# NBP16_Xilinx_Spartan-II_PQ208_Rev1_01.net
KiCad netlist of a schematic drawn in Altium Designer
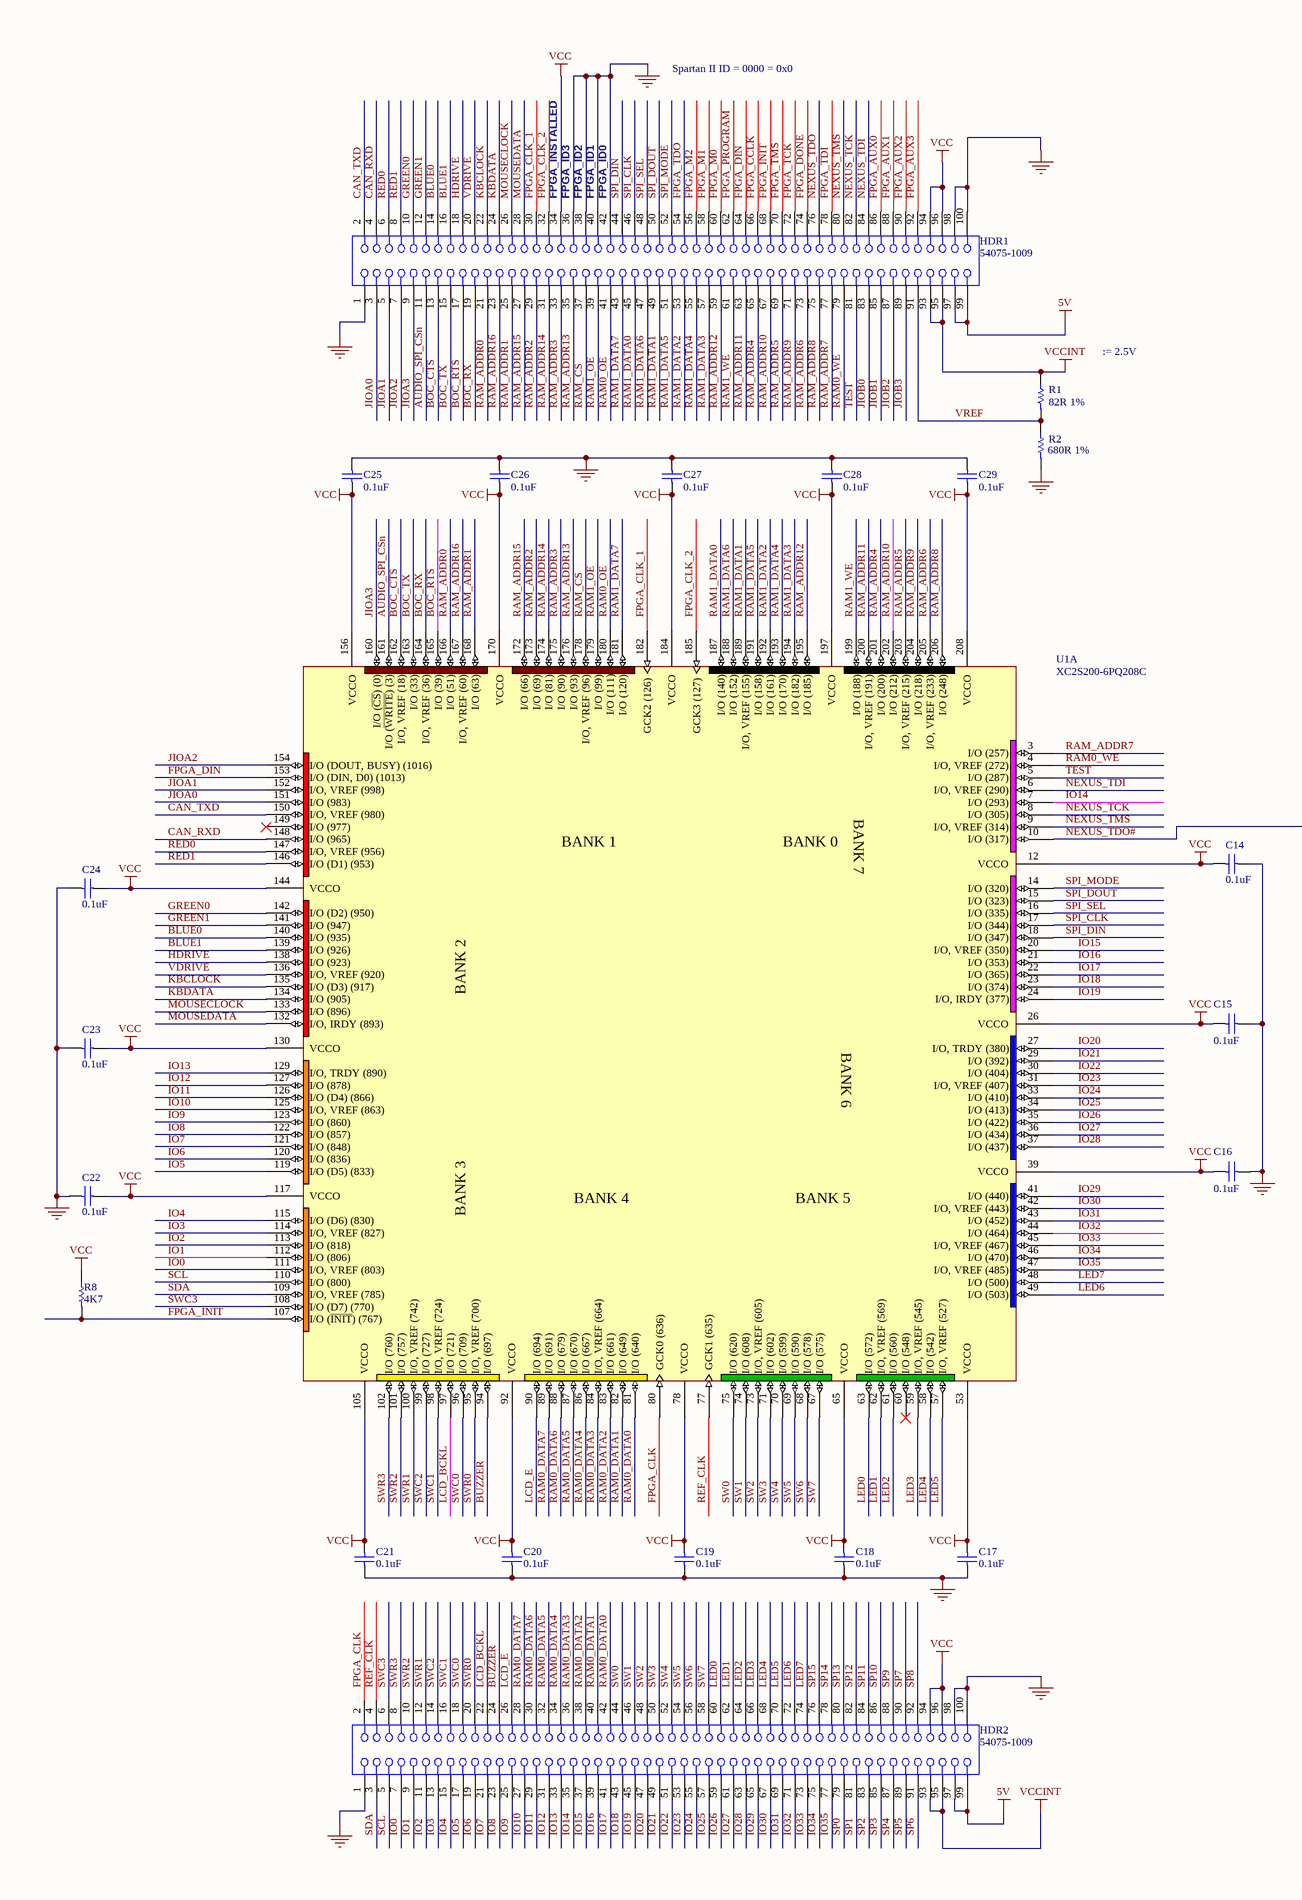
[diagram p0: NBP16 Xilinx Spartan-II PQ208 Rev1.01.SchDoc, left]
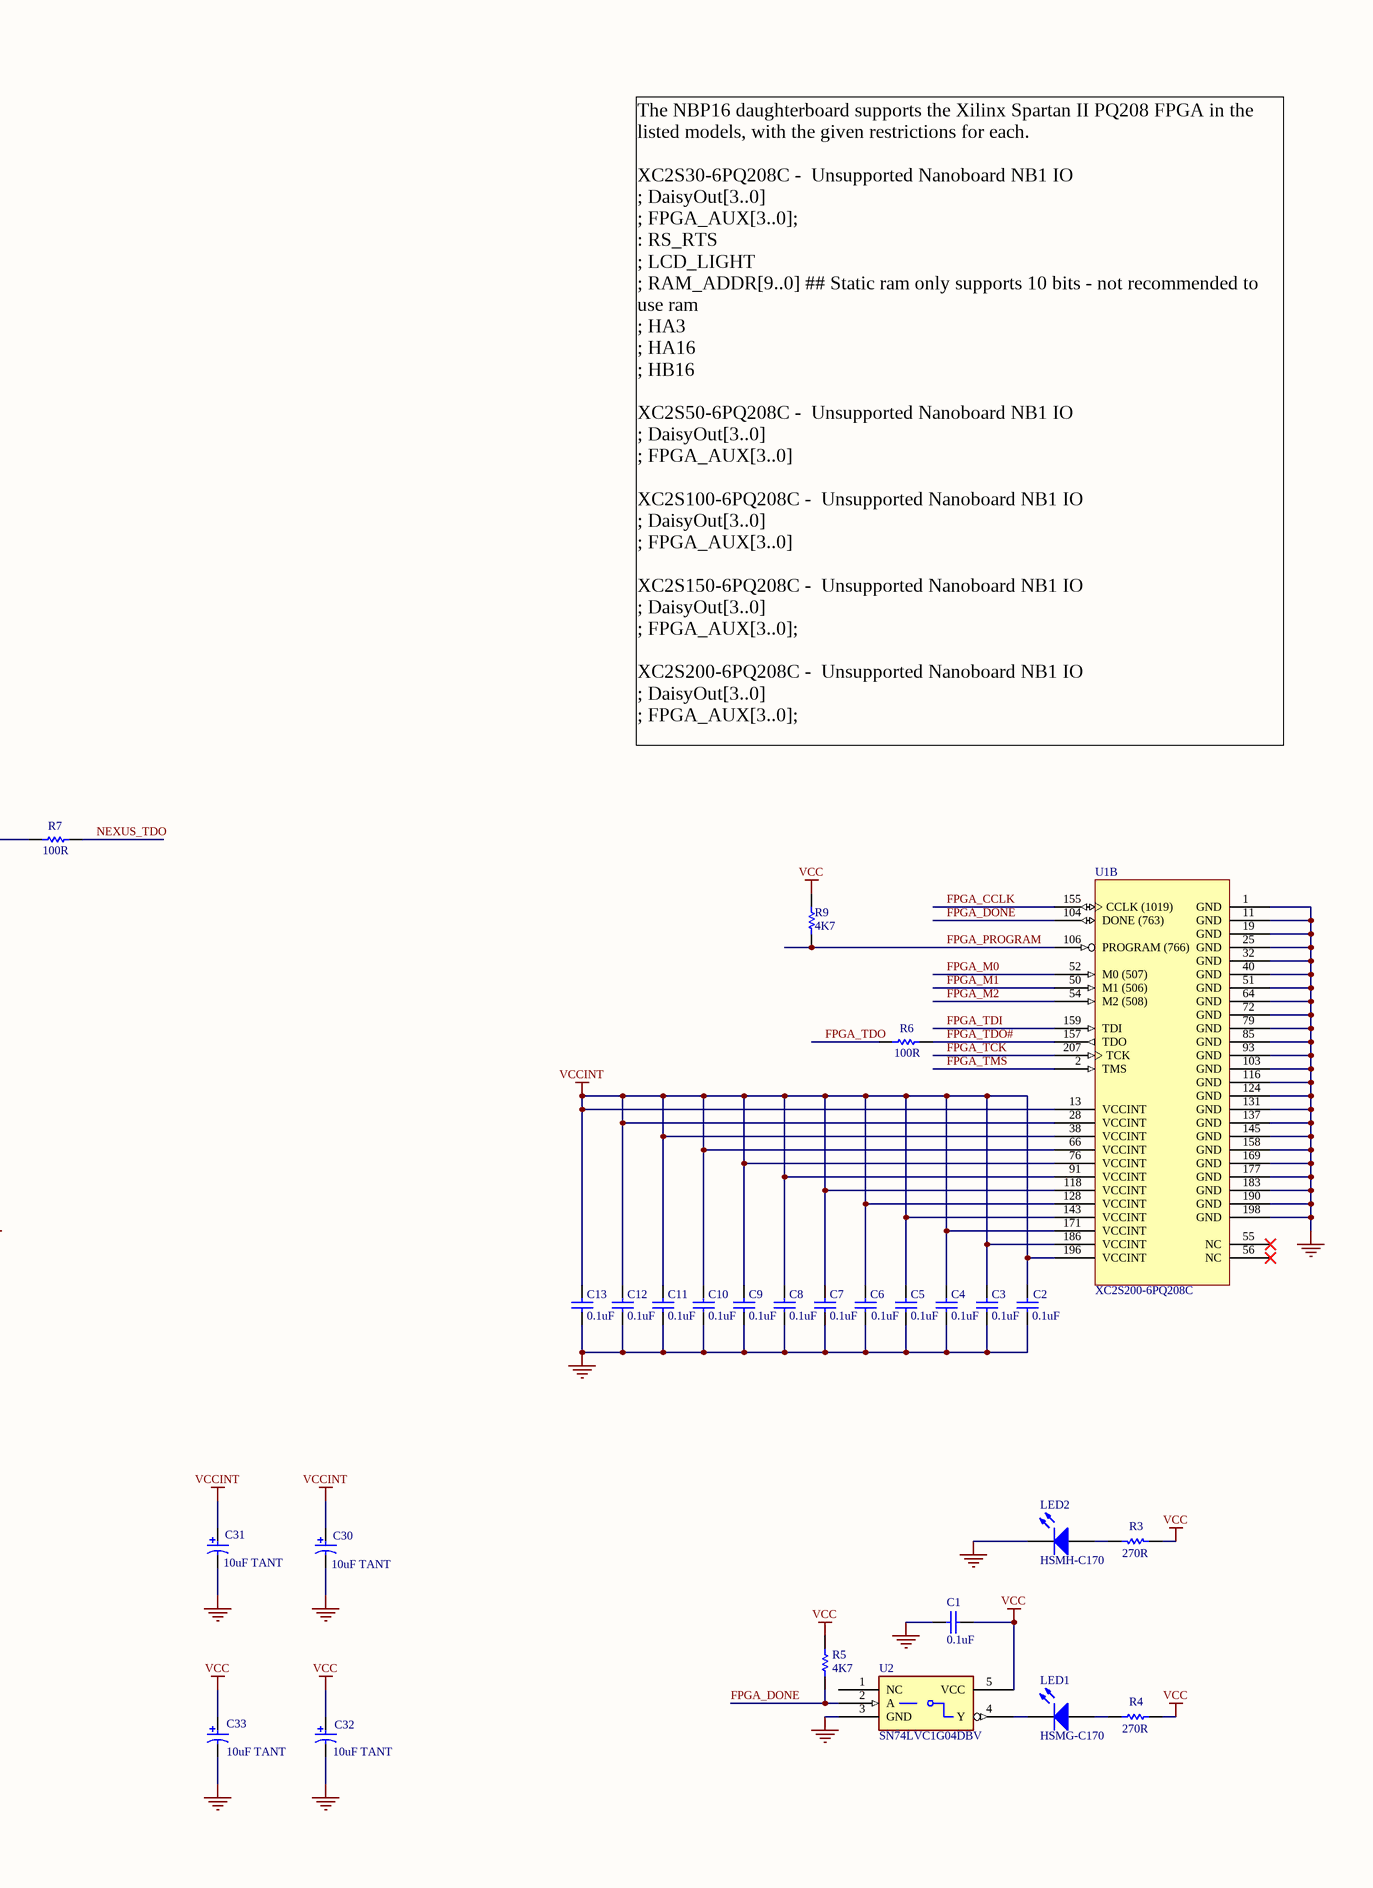
[diagram p1: NBP16 Xilinx Spartan-II PQ208 Rev1.01.SchDoc, right]

(export (version "E")
  (design (tool "Eeschema 10.0.6"))
  (components
    (comp (ref "C1")
      (value "0.1uF")
      (footprint "CC2012-0805")
      (description "Capacitor")
      (libsource (lib "PassiveSMD") (part "CAP"))
    )
    (comp (ref "C2")
      (value "0.1uF")
      (footprint "CC1608-0603")
      (description "Capacitor")
      (libsource (lib "PassiveSMD") (part "CAP"))
    )
    (comp (ref "C3")
      (value "0.1uF")
      (footprint "CC1608-0603")
      (description "Capacitor")
      (libsource (lib "PassiveSMD") (part "CAP"))
    )
    (comp (ref "C4")
      (value "0.1uF")
      (footprint "CC1608-0603")
      (description "Capacitor")
      (libsource (lib "PassiveSMD") (part "CAP"))
    )
    (comp (ref "C5")
      (value "0.1uF")
      (footprint "CC1608-0603")
      (description "Capacitor")
      (libsource (lib "PassiveSMD") (part "CAP"))
    )
    (comp (ref "C6")
      (value "0.1uF")
      (footprint "CC1608-0603")
      (description "Capacitor")
      (libsource (lib "PassiveSMD") (part "CAP"))
    )
    (comp (ref "C7")
      (value "0.1uF")
      (footprint "CC1608-0603")
      (description "Capacitor")
      (libsource (lib "PassiveSMD") (part "CAP"))
    )
    (comp (ref "C8")
      (value "0.1uF")
      (footprint "CC1608-0603")
      (description "Capacitor")
      (libsource (lib "PassiveSMD") (part "CAP"))
    )
    (comp (ref "C9")
      (value "0.1uF")
      (footprint "CC1608-0603")
      (description "Capacitor")
      (libsource (lib "PassiveSMD") (part "CAP"))
    )
    (comp (ref "C10")
      (value "0.1uF")
      (footprint "CC1608-0603")
      (description "Capacitor")
      (libsource (lib "PassiveSMD") (part "CAP"))
    )
    (comp (ref "C11")
      (value "0.1uF")
      (footprint "CC1608-0603")
      (description "Capacitor")
      (libsource (lib "PassiveSMD") (part "CAP"))
    )
    (comp (ref "C12")
      (value "0.1uF")
      (footprint "CC1608-0603")
      (description "Capacitor")
      (libsource (lib "PassiveSMD") (part "CAP"))
    )
    (comp (ref "C13")
      (value "0.1uF")
      (footprint "CC1608-0603")
      (description "Capacitor")
      (libsource (lib "PassiveSMD") (part "CAP"))
    )
    (comp (ref "C14")
      (value "0.1uF")
      (footprint "CC1608-0603")
      (description "Capacitor")
      (libsource (lib "PassiveSMD") (part "CAP"))
    )
    (comp (ref "C15")
      (value "0.1uF")
      (footprint "CC1608-0603")
      (description "Capacitor")
      (libsource (lib "PassiveSMD") (part "CAP"))
    )
    (comp (ref "C16")
      (value "0.1uF")
      (footprint "CC1608-0603")
      (description "Capacitor")
      (libsource (lib "PassiveSMD") (part "CAP"))
    )
    (comp (ref "C17")
      (value "0.1uF")
      (footprint "CC1608-0603")
      (description "Capacitor")
      (libsource (lib "PassiveSMD") (part "CAP"))
    )
    (comp (ref "C18")
      (value "0.1uF")
      (footprint "CC1608-0603")
      (description "Capacitor")
      (libsource (lib "PassiveSMD") (part "CAP"))
    )
    (comp (ref "C19")
      (value "0.1uF")
      (footprint "CC1608-0603")
      (description "Capacitor")
      (libsource (lib "PassiveSMD") (part "CAP"))
    )
    (comp (ref "C20")
      (value "0.1uF")
      (footprint "CC1608-0603")
      (description "Capacitor")
      (libsource (lib "PassiveSMD") (part "CAP"))
    )
    (comp (ref "C21")
      (value "0.1uF")
      (footprint "CC1608-0603")
      (description "Capacitor")
      (libsource (lib "PassiveSMD") (part "CAP"))
    )
    (comp (ref "C22")
      (value "0.1uF")
      (footprint "CC1608-0603")
      (description "Capacitor")
      (libsource (lib "PassiveSMD") (part "CAP"))
    )
    (comp (ref "C23")
      (value "0.1uF")
      (footprint "CC1608-0603")
      (description "Capacitor")
      (libsource (lib "PassiveSMD") (part "CAP"))
    )
    (comp (ref "C24")
      (value "0.1uF")
      (footprint "CC1608-0603")
      (description "Capacitor")
      (libsource (lib "PassiveSMD") (part "CAP"))
    )
    (comp (ref "C25")
      (value "0.1uF")
      (footprint "CC1608-0603")
      (description "Capacitor")
      (libsource (lib "PassiveSMD") (part "CAP"))
    )
    (comp (ref "C26")
      (value "0.1uF")
      (footprint "CC1608-0603")
      (description "Capacitor")
      (libsource (lib "PassiveSMD") (part "CAP"))
    )
    (comp (ref "C27")
      (value "0.1uF")
      (footprint "CC1608-0603")
      (description "Capacitor")
      (libsource (lib "PassiveSMD") (part "CAP"))
    )
    (comp (ref "C28")
      (value "0.1uF")
      (footprint "CC1608-0603")
      (description "Capacitor")
      (libsource (lib "PassiveSMD") (part "CAP"))
    )
    (comp (ref "C29")
      (value "0.1uF")
      (footprint "CC1608-0603")
      (description "Capacitor")
      (libsource (lib "PassiveSMD") (part "CAP"))
    )
    (comp (ref "C30")
      (value "10uF TANT")
      (footprint "MCCT-B")
      (description "Polar Capacitor")
      (libsource (lib "PassiveSMD") (part "CAP_POLAR"))
    )
    (comp (ref "C31")
      (value "10uF TANT")
      (footprint "MCCT-B")
      (description "Polar Capacitor")
      (libsource (lib "PassiveSMD") (part "CAP_POLAR"))
    )
    (comp (ref "C32")
      (value "10uF TANT")
      (footprint "MCCT-B")
      (description "Polar Capacitor")
      (libsource (lib "PassiveSMD") (part "CAP_POLAR"))
    )
    (comp (ref "C33")
      (value "10uF TANT")
      (footprint "MCCT-B")
      (description "Polar Capacitor")
      (libsource (lib "PassiveSMD") (part "CAP_POLAR"))
    )
    (comp (ref "HDR1")
      (value "54075-1009")
      (footprint "54075")
      (fields
        (field (name "MANUFACTURER") "Molex")
        (field (name "VOLTAGE") "100V")
        (field (name "PUBLISHER") "Altium Limited")
      )
      (libsource (lib "Altium Nanoboard Project") (part "54075-1009"))
    )
    (comp (ref "HDR2")
      (value "54075-1009")
      (footprint "54075")
      (fields
        (field (name "MANUFACTURER") "Molex")
        (field (name "VOLTAGE") "100V")
        (field (name "PUBLISHER") "Altium Limited")
      )
      (libsource (lib "Altium Nanoboard Project") (part "54075-1009"))
    )
    (comp (ref "LED1")
      (value "HSMG-C170")
      (footprint "SMD _LED")
      (description "Typical RED GaAs SMD LED Agilent make")
      (fields (field (name "MANUFACTURER") "Generic Components") (field (name "PUBLISHER") "Altium Limited"))
      (libsource (lib "Switches and display") (part "HSMX-C670"))
    )
    (comp (ref "LED2")
      (value "HSMH-C170")
      (footprint "SMD _LED")
      (description "Typical RED GaAs SMD LED Agilent make")
      (fields (field (name "MANUFACTURER") "Generic Components") (field (name "PUBLISHER") "Altium Limited"))
      (libsource (lib "Switches and display") (part "HSMX-C670"))
    )
    (comp (ref "R1")
      (value "82R 1%")
      (footprint "CC2012-0805")
      (description "Resistor")
      (libsource (lib "PassiveSMD") (part "RES"))
    )
    (comp (ref "R2")
      (value "680R 1%")
      (footprint "CC2012-0805")
      (description "Resistor")
      (libsource (lib "PassiveSMD") (part "RES"))
    )
    (comp (ref "R3")
      (value "270R")
      (footprint "CC2012-0805")
      (description "Resistor")
      (libsource (lib "PassiveSMD") (part "RES"))
    )
    (comp (ref "R4")
      (value "270R")
      (footprint "CC2012-0805")
      (description "Resistor")
      (libsource (lib "PassiveSMD") (part "RES"))
    )
    (comp (ref "R5")
      (value "4K7")
      (footprint "CC2012-0805")
      (description "Resistor")
      (libsource (lib "PassiveSMD") (part "RES"))
    )
    (comp (ref "R6")
      (value "100R")
      (footprint "CC2012-0805")
      (description "Resistor")
      (libsource (lib "PassiveSMD") (part "RES"))
    )
    (comp (ref "R7")
      (value "100R")
      (footprint "CC2012-0805")
      (description "Resistor")
      (libsource (lib "PassiveSMD") (part "RES"))
    )
    (comp (ref "R8")
      (value "4K7")
      (footprint "CC2012-0805")
      (description "Resistor")
      (libsource (lib "PassiveSMD") (part "RES"))
    )
    (comp (ref "R9")
      (value "4K7")
      (footprint "CC2012-0805")
      (description "Resistor")
      (libsource (lib "PassiveSMD") (part "RES"))
    )
    (comp (ref "U1")
      (value "XC2S200-6PQ208C")
      (footprint "F-QFP28X28-G208/P.5N")
      (description "Spartan-II 2.5V FPGA, 208-Pin PQFP, Higher Performance, Commercial Grade")
      (fields (field (name "PUBLISHER") "Altium Limited"))
      (libsource (lib "Xilinx Spartan-II") (part "XC2S200-6PQ208C"))
    )
    (comp (ref "U2")
      (value "SN74LVC1G04DBV")
      (footprint "SO-G5/P.95")
      (fields (field (name "MANUFACTURER") "TI"))
      (libsource (lib "Philips1GLogic") (part "SN74AHC1G04DBVR"))
    )
  )
  (nets
    (net (code "1") (name "/AUDIO_SPI_CSn") (class "Default")
      (node (ref "HDR1") (pin "11") (pinfunction "11_11") (pintype "passive"))
      (node (ref "U1") (pin "161") (pinfunction "I/O_(~{WRITE})_(3)_161") (pintype "bidirectional"))
    )
    (net (code "2") (name "/BLUE0") (class "Default")
      (node (ref "HDR1") (pin "14") (pinfunction "14_14") (pintype "passive"))
      (node (ref "U1") (pin "140") (pinfunction "I/O_(935)_140") (pintype "bidirectional"))
    )
    (net (code "3") (name "/BLUE1") (class "Default")
      (node (ref "HDR1") (pin "16") (pinfunction "16_16") (pintype "passive"))
      (node (ref "U1") (pin "139") (pinfunction "I/O_(926)_139") (pintype "bidirectional"))
    )
    (net (code "4") (name "/BOC_CTS") (class "Default")
      (node (ref "HDR1") (pin "13") (pinfunction "13_13") (pintype "passive"))
      (node (ref "U1") (pin "162") (pinfunction "I/O,_VREF_(18)_162") (pintype "bidirectional"))
    )
    (net (code "5") (name "/BOC_RTS") (class "Default")
      (node (ref "HDR1") (pin "17") (pinfunction "17_17") (pintype "passive"))
      (node (ref "U1") (pin "165") (pinfunction "I/O_(39)_165") (pintype "bidirectional"))
    )
    (net (code "6") (name "/BOC_RX") (class "Default")
      (node (ref "HDR1") (pin "19") (pinfunction "19_19") (pintype "passive"))
      (node (ref "U1") (pin "164") (pinfunction "I/O,_VREF_(36)_164") (pintype "bidirectional"))
    )
    (net (code "7") (name "/BOC_TX") (class "Default")
      (node (ref "HDR1") (pin "15") (pinfunction "15_15") (pintype "passive"))
      (node (ref "U1") (pin "163") (pinfunction "I/O_(33)_163") (pintype "bidirectional"))
    )
    (net (code "8") (name "/BUZZER") (class "Default")
      (node (ref "HDR2") (pin "24") (pinfunction "24_24") (pintype "passive"))
      (node (ref "U1") (pin "94") (pinfunction "I/O_(697)_94") (pintype "bidirectional"))
    )
    (net (code "9") (name "/CAN_RXD") (class "Default")
      (node (ref "HDR1") (pin "4") (pinfunction "4_4") (pintype "passive"))
      (node (ref "U1") (pin "148") (pinfunction "I/O_(965)_148") (pintype "bidirectional"))
    )
    (net (code "10") (name "/CAN_TXD") (class "Default")
      (node (ref "HDR1") (pin "2") (pinfunction "2_2") (pintype "passive"))
      (node (ref "U1") (pin "150") (pinfunction "I/O,_VREF_(980)_150") (pintype "bidirectional"))
    )
    (net (code "11") (name "/FPGA_AUX0") (class "Default")
      (node (ref "HDR1") (pin "86") (pinfunction "86_86") (pintype "passive"))
    )
    (net (code "12") (name "/FPGA_AUX1") (class "Default")
      (node (ref "HDR1") (pin "88") (pinfunction "88_88") (pintype "passive"))
    )
    (net (code "13") (name "/FPGA_AUX2") (class "Default")
      (node (ref "HDR1") (pin "90") (pinfunction "90_90") (pintype "passive"))
    )
    (net (code "14") (name "/FPGA_AUX3") (class "Default")
      (node (ref "HDR1") (pin "92") (pinfunction "92_92") (pintype "passive"))
    )
    (net (code "15") (name "/FPGA_CCLK") (class "Default")
      (node (ref "HDR1") (pin "66") (pinfunction "66_66") (pintype "passive"))
      (node (ref "U1") (pin "155") (pinfunction "CCLK_(1019)_155") (pintype "bidirectional"))
    )
    (net (code "16") (name "/FPGA_CLK") (class "Default")
      (node (ref "HDR2") (pin "2") (pinfunction "2_2") (pintype "passive"))
      (node (ref "U1") (pin "80") (pinfunction "GCK0_(636)_80") (pintype "input"))
    )
    (net (code "17") (name "/FPGA_CLK_1") (class "Default")
      (node (ref "HDR1") (pin "30") (pinfunction "30_30") (pintype "passive"))
      (node (ref "U1") (pin "182") (pinfunction "GCK2_(126)_182") (pintype "input"))
    )
    (net (code "18") (name "/FPGA_CLK_2") (class "Default")
      (node (ref "HDR1") (pin "32") (pinfunction "32_32") (pintype "passive"))
      (node (ref "U1") (pin "185") (pinfunction "GCK3_(127)_185") (pintype "input"))
    )
    (net (code "19") (name "/FPGA_DIN") (class "Default")
      (node (ref "HDR1") (pin "64") (pinfunction "64_64") (pintype "passive"))
      (node (ref "U1") (pin "153") (pinfunction "I/O_(DIN,_D0)_(1013)_153") (pintype "bidirectional"))
    )
    (net (code "20") (name "/FPGA_DONE") (class "Default")
      (node (ref "HDR1") (pin "74") (pinfunction "74_74") (pintype "passive"))
      (node (ref "R5") (pin "2") (pinfunction "2_2") (pintype "passive"))
      (node (ref "U1") (pin "104") (pinfunction "DONE_(763)_104") (pintype "bidirectional"))
      (node (ref "U2") (pin "2") (pinfunction "A_2") (pintype "input"))
    )
    (net (code "21") (name "/FPGA_INIT") (class "Default")
      (node (ref "HDR1") (pin "68") (pinfunction "68_68") (pintype "passive"))
      (node (ref "R8") (pin "2") (pinfunction "2_2") (pintype "passive"))
      (node (ref "U1") (pin "107") (pinfunction "I/O_(~{INIT})_(767)_107") (pintype "bidirectional"))
    )
    (net (code "22") (name "/FPGA_M0") (class "Default")
      (node (ref "HDR1") (pin "60") (pinfunction "60_60") (pintype "passive"))
      (node (ref "U1") (pin "52") (pinfunction "M0_(507)_52") (pintype "input"))
    )
    (net (code "23") (name "/FPGA_M1") (class "Default")
      (node (ref "HDR1") (pin "58") (pinfunction "58_58") (pintype "passive"))
      (node (ref "U1") (pin "50") (pinfunction "M1_(506)_50") (pintype "input"))
    )
    (net (code "24") (name "/FPGA_M2") (class "Default")
      (node (ref "HDR1") (pin "56") (pinfunction "56_56") (pintype "passive"))
      (node (ref "U1") (pin "54") (pinfunction "M2_(508)_54") (pintype "input"))
    )
    (net (code "25") (name "/FPGA_PROGRAM") (class "Default")
      (node (ref "HDR1") (pin "62") (pinfunction "62_62") (pintype "passive"))
      (node (ref "R9") (pin "2") (pinfunction "2_2") (pintype "passive"))
      (node (ref "U1") (pin "106") (pinfunction "PROGRAM_(766)_106") (pintype "input"))
    )
    (net (code "26") (name "/FPGA_TCK") (class "Default")
      (node (ref "HDR1") (pin "72") (pinfunction "72_72") (pintype "passive"))
      (node (ref "U1") (pin "207") (pinfunction "TCK_207") (pintype "input"))
    )
    (net (code "27") (name "/FPGA_TDI") (class "Default")
      (node (ref "HDR1") (pin "78") (pinfunction "78_78") (pintype "passive"))
      (node (ref "U1") (pin "159") (pinfunction "TDI_159") (pintype "input"))
    )
    (net (code "28") (name "/FPGA_TDO") (class "Default")
      (node (ref "HDR1") (pin "54") (pinfunction "54_54") (pintype "passive"))
      (node (ref "R6") (pin "1") (pinfunction "1_1") (pintype "passive"))
    )
    (net (code "29") (name "/FPGA_TDO#") (class "Default")
      (node (ref "R6") (pin "2") (pinfunction "2_2") (pintype "passive"))
      (node (ref "U1") (pin "157") (pinfunction "TDO_157") (pintype "output"))
    )
    (net (code "30") (name "/FPGA_TMS") (class "Default")
      (node (ref "HDR1") (pin "70") (pinfunction "70_70") (pintype "passive"))
      (node (ref "U1") (pin "2") (pinfunction "TMS_2") (pintype "input"))
    )
    (net (code "31") (name "/GREEN0") (class "Default")
      (node (ref "HDR1") (pin "10") (pinfunction "10_10") (pintype "passive"))
      (node (ref "U1") (pin "142") (pinfunction "I/O_(D2)_(950)_142") (pintype "bidirectional"))
    )
    (net (code "32") (name "/GREEN1") (class "Default")
      (node (ref "HDR1") (pin "12") (pinfunction "12_12") (pintype "passive"))
      (node (ref "U1") (pin "141") (pinfunction "I/O_(947)_141") (pintype "bidirectional"))
    )
    (net (code "33") (name "/HDRIVE") (class "Default")
      (node (ref "HDR1") (pin "18") (pinfunction "18_18") (pintype "passive"))
      (node (ref "U1") (pin "138") (pinfunction "I/O_(923)_138") (pintype "bidirectional"))
    )
    (net (code "34") (name "/IO0") (class "Default")
      (node (ref "HDR2") (pin "7") (pinfunction "7_7") (pintype "passive"))
      (node (ref "U1") (pin "111") (pinfunction "I/O,_VREF_(803)_111") (pintype "bidirectional"))
    )
    (net (code "35") (name "/IO1") (class "Default")
      (node (ref "HDR2") (pin "9") (pinfunction "9_9") (pintype "passive"))
      (node (ref "U1") (pin "112") (pinfunction "I/O_(806)_112") (pintype "bidirectional"))
    )
    (net (code "36") (name "/IO2") (class "Default")
      (node (ref "HDR2") (pin "11") (pinfunction "11_11") (pintype "passive"))
      (node (ref "U1") (pin "113") (pinfunction "I/O_(818)_113") (pintype "bidirectional"))
    )
    (net (code "37") (name "/IO3") (class "Default")
      (node (ref "HDR2") (pin "13") (pinfunction "13_13") (pintype "passive"))
      (node (ref "U1") (pin "114") (pinfunction "I/O,_VREF_(827)_114") (pintype "bidirectional"))
    )
    (net (code "38") (name "/IO4") (class "Default")
      (node (ref "HDR2") (pin "15") (pinfunction "15_15") (pintype "passive"))
      (node (ref "U1") (pin "115") (pinfunction "I/O_(D6)_(830)_115") (pintype "bidirectional"))
    )
    (net (code "39") (name "/IO5") (class "Default")
      (node (ref "HDR2") (pin "17") (pinfunction "17_17") (pintype "passive"))
      (node (ref "U1") (pin "119") (pinfunction "I/O_(D5)_(833)_119") (pintype "bidirectional"))
    )
    (net (code "40") (name "/IO6") (class "Default")
      (node (ref "HDR2") (pin "19") (pinfunction "19_19") (pintype "passive"))
      (node (ref "U1") (pin "120") (pinfunction "I/O_(836)_120") (pintype "bidirectional"))
    )
    (net (code "41") (name "/IO7") (class "Default")
      (node (ref "HDR2") (pin "21") (pinfunction "21_21") (pintype "passive"))
      (node (ref "U1") (pin "121") (pinfunction "I/O_(848)_121") (pintype "bidirectional"))
    )
    (net (code "42") (name "/IO8") (class "Default")
      (node (ref "HDR2") (pin "23") (pinfunction "23_23") (pintype "passive"))
      (node (ref "U1") (pin "122") (pinfunction "I/O_(857)_122") (pintype "bidirectional"))
    )
    (net (code "43") (name "/IO9") (class "Default")
      (node (ref "HDR2") (pin "25") (pinfunction "25_25") (pintype "passive"))
      (node (ref "U1") (pin "123") (pinfunction "I/O_(860)_123") (pintype "bidirectional"))
    )
    (net (code "44") (name "/IO10") (class "Default")
      (node (ref "HDR2") (pin "27") (pinfunction "27_27") (pintype "passive"))
      (node (ref "U1") (pin "125") (pinfunction "I/O,_VREF_(863)_125") (pintype "bidirectional"))
    )
    (net (code "45") (name "/IO11") (class "Default")
      (node (ref "HDR2") (pin "29") (pinfunction "29_29") (pintype "passive"))
      (node (ref "U1") (pin "126") (pinfunction "I/O_(D4)_(866)_126") (pintype "bidirectional"))
    )
    (net (code "46") (name "/IO12") (class "Default")
      (node (ref "HDR2") (pin "31") (pinfunction "31_31") (pintype "passive"))
      (node (ref "U1") (pin "127") (pinfunction "I/O_(878)_127") (pintype "bidirectional"))
    )
    (net (code "47") (name "/IO13") (class "Default")
      (node (ref "HDR2") (pin "33") (pinfunction "33_33") (pintype "passive"))
      (node (ref "U1") (pin "129") (pinfunction "I/O,_TRDY_(890)_129") (pintype "bidirectional"))
    )
    (net (code "48") (name "/IO14") (class "Default")
      (node (ref "HDR2") (pin "35") (pinfunction "35_35") (pintype "passive"))
      (node (ref "U1") (pin "7") (pinfunction "I/O_(293)_7") (pintype "bidirectional"))
    )
    (net (code "49") (name "/IO15") (class "Default")
      (node (ref "HDR2") (pin "37") (pinfunction "37_37") (pintype "passive"))
      (node (ref "U1") (pin "20") (pinfunction "I/O,_VREF_(350)_20") (pintype "bidirectional"))
    )
    (net (code "50") (name "/IO16") (class "Default")
      (node (ref "HDR2") (pin "39") (pinfunction "39_39") (pintype "passive"))
      (node (ref "U1") (pin "21") (pinfunction "I/O_(353)_21") (pintype "bidirectional"))
    )
    (net (code "51") (name "/IO17") (class "Default")
      (node (ref "HDR2") (pin "41") (pinfunction "41_41") (pintype "passive"))
      (node (ref "U1") (pin "22") (pinfunction "I/O_(365)_22") (pintype "bidirectional"))
    )
    (net (code "52") (name "/IO18") (class "Default")
      (node (ref "HDR2") (pin "43") (pinfunction "43_43") (pintype "passive"))
      (node (ref "U1") (pin "23") (pinfunction "I/O_(374)_23") (pintype "bidirectional"))
    )
    (net (code "53") (name "/IO19") (class "Default")
      (node (ref "HDR2") (pin "45") (pinfunction "45_45") (pintype "passive"))
      (node (ref "U1") (pin "24") (pinfunction "I/O,_IRDY_(377)_24") (pintype "bidirectional"))
    )
    (net (code "54") (name "/IO20") (class "Default")
      (node (ref "HDR2") (pin "47") (pinfunction "47_47") (pintype "passive"))
      (node (ref "U1") (pin "27") (pinfunction "I/O,_TRDY_(380)_27") (pintype "bidirectional"))
    )
    (net (code "55") (name "/IO21") (class "Default")
      (node (ref "HDR2") (pin "49") (pinfunction "49_49") (pintype "passive"))
      (node (ref "U1") (pin "29") (pinfunction "I/O_(392)_29") (pintype "bidirectional"))
    )
    (net (code "56") (name "/IO22") (class "Default")
      (node (ref "HDR2") (pin "51") (pinfunction "51_51") (pintype "passive"))
      (node (ref "U1") (pin "30") (pinfunction "I/O_(404)_30") (pintype "bidirectional"))
    )
    (net (code "57") (name "/IO23") (class "Default")
      (node (ref "HDR2") (pin "53") (pinfunction "53_53") (pintype "passive"))
      (node (ref "U1") (pin "31") (pinfunction "I/O,_VREF_(407)_31") (pintype "bidirectional"))
    )
    (net (code "58") (name "/IO24") (class "Default")
      (node (ref "HDR2") (pin "55") (pinfunction "55_55") (pintype "passive"))
      (node (ref "U1") (pin "33") (pinfunction "I/O_(410)_33") (pintype "bidirectional"))
    )
    (net (code "59") (name "/IO25") (class "Default")
      (node (ref "HDR2") (pin "57") (pinfunction "57_57") (pintype "passive"))
      (node (ref "U1") (pin "34") (pinfunction "I/O_(413)_34") (pintype "bidirectional"))
    )
    (net (code "60") (name "/IO26") (class "Default")
      (node (ref "HDR2") (pin "59") (pinfunction "59_59") (pintype "passive"))
      (node (ref "U1") (pin "35") (pinfunction "I/O_(422)_35") (pintype "bidirectional"))
    )
    (net (code "61") (name "/IO27") (class "Default")
      (node (ref "HDR2") (pin "61") (pinfunction "61_61") (pintype "passive"))
      (node (ref "U1") (pin "36") (pinfunction "I/O_(434)_36") (pintype "bidirectional"))
    )
    (net (code "62") (name "/IO28") (class "Default")
      (node (ref "HDR2") (pin "63") (pinfunction "63_63") (pintype "passive"))
      (node (ref "U1") (pin "37") (pinfunction "I/O_(437)_37") (pintype "bidirectional"))
    )
    (net (code "63") (name "/IO29") (class "Default")
      (node (ref "HDR2") (pin "65") (pinfunction "65_65") (pintype "passive"))
      (node (ref "U1") (pin "41") (pinfunction "I/O_(440)_41") (pintype "bidirectional"))
    )
    (net (code "64") (name "/IO30") (class "Default")
      (node (ref "HDR2") (pin "67") (pinfunction "67_67") (pintype "passive"))
      (node (ref "U1") (pin "42") (pinfunction "I/O,_VREF_(443)_42") (pintype "bidirectional"))
    )
    (net (code "65") (name "/IO31") (class "Default")
      (node (ref "HDR2") (pin "69") (pinfunction "69_69") (pintype "passive"))
      (node (ref "U1") (pin "43") (pinfunction "I/O_(452)_43") (pintype "bidirectional"))
    )
    (net (code "66") (name "/IO32") (class "Default")
      (node (ref "HDR2") (pin "71") (pinfunction "71_71") (pintype "passive"))
      (node (ref "U1") (pin "44") (pinfunction "I/O_(464)_44") (pintype "bidirectional"))
    )
    (net (code "67") (name "/IO33") (class "Default")
      (node (ref "HDR2") (pin "73") (pinfunction "73_73") (pintype "passive"))
      (node (ref "U1") (pin "45") (pinfunction "I/O,_VREF_(467)_45") (pintype "bidirectional"))
    )
    (net (code "68") (name "/IO34") (class "Default")
      (node (ref "HDR2") (pin "75") (pinfunction "75_75") (pintype "passive"))
      (node (ref "U1") (pin "46") (pinfunction "I/O_(470)_46") (pintype "bidirectional"))
    )
    (net (code "69") (name "/IO35") (class "Default")
      (node (ref "HDR2") (pin "77") (pinfunction "77_77") (pintype "passive"))
      (node (ref "U1") (pin "47") (pinfunction "I/O,_VREF_(485)_47") (pintype "bidirectional"))
    )
    (net (code "70") (name "/JIOA0") (class "Default")
      (node (ref "HDR1") (pin "3") (pinfunction "3_3") (pintype "passive"))
      (node (ref "U1") (pin "151") (pinfunction "I/O_(983)_151") (pintype "bidirectional"))
    )
    (net (code "71") (name "/JIOA1") (class "Default")
      (node (ref "HDR1") (pin "5") (pinfunction "5_5") (pintype "passive"))
      (node (ref "U1") (pin "152") (pinfunction "I/O,_VREF_(998)_152") (pintype "bidirectional"))
    )
    (net (code "72") (name "/JIOA2") (class "Default")
      (node (ref "HDR1") (pin "7") (pinfunction "7_7") (pintype "passive"))
      (node (ref "U1") (pin "154") (pinfunction "I/O_(DOUT,_BUSY)_(1016)_154") (pintype "bidirectional"))
    )
    (net (code "73") (name "/JIOA3") (class "Default")
      (node (ref "HDR1") (pin "9") (pinfunction "9_9") (pintype "passive"))
      (node (ref "U1") (pin "160") (pinfunction "I/O_(~{CS})_(0)_160") (pintype "bidirectional"))
    )
    (net (code "74") (name "/JIOB0") (class "Default")
      (node (ref "HDR1") (pin "83") (pinfunction "83_83") (pintype "passive"))
    )
    (net (code "75") (name "/JIOB1") (class "Default")
      (node (ref "HDR1") (pin "85") (pinfunction "85_85") (pintype "passive"))
    )
    (net (code "76") (name "/JIOB2") (class "Default")
      (node (ref "HDR1") (pin "87") (pinfunction "87_87") (pintype "passive"))
    )
    (net (code "77") (name "/JIOB3") (class "Default")
      (node (ref "HDR1") (pin "89") (pinfunction "89_89") (pintype "passive"))
    )
    (net (code "78") (name "/KBCLOCK") (class "Default")
      (node (ref "HDR1") (pin "22") (pinfunction "22_22") (pintype "passive"))
      (node (ref "U1") (pin "135") (pinfunction "I/O_(D3)_(917)_135") (pintype "bidirectional"))
    )
    (net (code "79") (name "/KBDATA") (class "Default")
      (node (ref "HDR1") (pin "24") (pinfunction "24_24") (pintype "passive"))
      (node (ref "U1") (pin "134") (pinfunction "I/O_(905)_134") (pintype "bidirectional"))
    )
    (net (code "80") (name "/LCD_BCKL") (class "Default")
      (node (ref "HDR2") (pin "22") (pinfunction "22_22") (pintype "passive"))
      (node (ref "U1") (pin "97") (pinfunction "I/O_(721)_97") (pintype "bidirectional"))
    )
    (net (code "81") (name "/LCD_E") (class "Default")
      (node (ref "HDR2") (pin "26") (pinfunction "26_26") (pintype "passive"))
      (node (ref "U1") (pin "90") (pinfunction "I/O_(694)_90") (pintype "bidirectional"))
    )
    (net (code "82") (name "/LED0") (class "Default")
      (node (ref "HDR2") (pin "60") (pinfunction "60_60") (pintype "passive"))
      (node (ref "U1") (pin "63") (pinfunction "I/O_(572)_63") (pintype "bidirectional"))
    )
    (net (code "83") (name "/LED1") (class "Default")
      (node (ref "HDR2") (pin "62") (pinfunction "62_62") (pintype "passive"))
      (node (ref "U1") (pin "62") (pinfunction "I/O,_VREF_(569)_62") (pintype "bidirectional"))
    )
    (net (code "84") (name "/LED2") (class "Default")
      (node (ref "HDR2") (pin "64") (pinfunction "64_64") (pintype "passive"))
      (node (ref "U1") (pin "61") (pinfunction "I/O_(560)_61") (pintype "bidirectional"))
    )
    (net (code "85") (name "/LED3") (class "Default")
      (node (ref "HDR2") (pin "66") (pinfunction "66_66") (pintype "passive"))
      (node (ref "U1") (pin "59") (pinfunction "I/O,_VREF_(545)_59") (pintype "bidirectional"))
    )
    (net (code "86") (name "/LED4") (class "Default")
      (node (ref "HDR2") (pin "68") (pinfunction "68_68") (pintype "passive"))
      (node (ref "U1") (pin "58") (pinfunction "I/O_(542)_58") (pintype "bidirectional"))
    )
    (net (code "87") (name "/LED5") (class "Default")
      (node (ref "HDR2") (pin "70") (pinfunction "70_70") (pintype "passive"))
      (node (ref "U1") (pin "57") (pinfunction "I/O,_VREF_(527)_57") (pintype "bidirectional"))
    )
    (net (code "88") (name "/LED6") (class "Default")
      (node (ref "HDR2") (pin "72") (pinfunction "72_72") (pintype "passive"))
      (node (ref "U1") (pin "49") (pinfunction "I/O_(503)_49") (pintype "bidirectional"))
    )
    (net (code "89") (name "/LED7") (class "Default")
      (node (ref "HDR2") (pin "74") (pinfunction "74_74") (pintype "passive"))
      (node (ref "U1") (pin "48") (pinfunction "I/O_(500)_48") (pintype "bidirectional"))
    )
    (net (code "90") (name "/MOUSECLOCK") (class "Default")
      (node (ref "HDR1") (pin "26") (pinfunction "26_26") (pintype "passive"))
      (node (ref "U1") (pin "133") (pinfunction "I/O_(896)_133") (pintype "bidirectional"))
    )
    (net (code "91") (name "/MOUSEDATA") (class "Default")
      (node (ref "HDR1") (pin "28") (pinfunction "28_28") (pintype "passive"))
      (node (ref "U1") (pin "132") (pinfunction "I/O,_IRDY_(893)_132") (pintype "bidirectional"))
    )
    (net (code "92") (name "/NEXUS_TCK") (class "Default")
      (node (ref "HDR1") (pin "82") (pinfunction "82_82") (pintype "passive"))
      (node (ref "U1") (pin "8") (pinfunction "I/O_(305)_8") (pintype "bidirectional"))
    )
    (net (code "93") (name "/NEXUS_TDI") (class "Default")
      (node (ref "HDR1") (pin "84") (pinfunction "84_84") (pintype "passive"))
      (node (ref "U1") (pin "6") (pinfunction "I/O,_VREF_(290)_6") (pintype "bidirectional"))
    )
    (net (code "94") (name "/NEXUS_TDO") (class "Default")
      (node (ref "HDR1") (pin "76") (pinfunction "76_76") (pintype "passive"))
      (node (ref "R7") (pin "2") (pinfunction "2_2") (pintype "passive"))
    )
    (net (code "95") (name "/NEXUS_TDO#") (class "Default")
      (node (ref "R7") (pin "1") (pinfunction "1_1") (pintype "passive"))
      (node (ref "U1") (pin "10") (pinfunction "I/O_(317)_10") (pintype "bidirectional"))
    )
    (net (code "96") (name "/NEXUS_TMS") (class "Default")
      (node (ref "HDR1") (pin "80") (pinfunction "80_80") (pintype "passive"))
      (node (ref "U1") (pin "9") (pinfunction "I/O,_VREF_(314)_9") (pintype "bidirectional"))
    )
    (net (code "97") (name "/RAM0_DATA0") (class "Default")
      (node (ref "HDR2") (pin "42") (pinfunction "42_42") (pintype "passive"))
      (node (ref "U1") (pin "81") (pinfunction "I/O_(640)_81") (pintype "bidirectional"))
    )
    (net (code "98") (name "/RAM0_DATA1") (class "Default")
      (node (ref "HDR2") (pin "40") (pinfunction "40_40") (pintype "passive"))
      (node (ref "U1") (pin "82") (pinfunction "I/O_(649)_82") (pintype "bidirectional"))
    )
    (net (code "99") (name "/RAM0_DATA2") (class "Default")
      (node (ref "HDR2") (pin "38") (pinfunction "38_38") (pintype "passive"))
      (node (ref "U1") (pin "83") (pinfunction "I/O_(661)_83") (pintype "bidirectional"))
    )
    (net (code "100") (name "/RAM0_DATA3") (class "Default")
      (node (ref "HDR2") (pin "36") (pinfunction "36_36") (pintype "passive"))
      (node (ref "U1") (pin "84") (pinfunction "I/O,_VREF_(664)_84") (pintype "bidirectional"))
    )
    (net (code "101") (name "/RAM0_DATA4") (class "Default")
      (node (ref "HDR2") (pin "34") (pinfunction "34_34") (pintype "passive"))
      (node (ref "U1") (pin "86") (pinfunction "I/O_(667)_86") (pintype "bidirectional"))
    )
    (net (code "102") (name "/RAM0_DATA5") (class "Default")
      (node (ref "HDR2") (pin "32") (pinfunction "32_32") (pintype "passive"))
      (node (ref "U1") (pin "87") (pinfunction "I/O_(670)_87") (pintype "bidirectional"))
    )
    (net (code "103") (name "/RAM0_DATA6") (class "Default")
      (node (ref "HDR2") (pin "30") (pinfunction "30_30") (pintype "passive"))
      (node (ref "U1") (pin "88") (pinfunction "I/O_(679)_88") (pintype "bidirectional"))
    )
    (net (code "104") (name "/RAM0_DATA7") (class "Default")
      (node (ref "HDR2") (pin "28") (pinfunction "28_28") (pintype "passive"))
      (node (ref "U1") (pin "89") (pinfunction "I/O_(691)_89") (pintype "bidirectional"))
    )
    (net (code "105") (name "/RAM0_OE") (class "Default")
      (node (ref "HDR1") (pin "41") (pinfunction "41_41") (pintype "passive"))
      (node (ref "U1") (pin "180") (pinfunction "I/O_(111)_180") (pintype "bidirectional"))
    )
    (net (code "106") (name "/RAM0_WE") (class "Default")
      (node (ref "HDR1") (pin "79") (pinfunction "79_79") (pintype "passive"))
      (node (ref "U1") (pin "4") (pinfunction "I/O,_VREF_(272)_4") (pintype "bidirectional"))
    )
    (net (code "107") (name "/RAM1_DATA0") (class "Default")
      (node (ref "HDR1") (pin "45") (pinfunction "45_45") (pintype "passive"))
      (node (ref "U1") (pin "187") (pinfunction "I/O_(140)_187") (pintype "bidirectional"))
    )
    (net (code "108") (name "/RAM1_DATA1") (class "Default")
      (node (ref "HDR1") (pin "49") (pinfunction "49_49") (pintype "passive"))
      (node (ref "U1") (pin "189") (pinfunction "I/O,_VREF_(155)_189") (pintype "bidirectional"))
    )
    (net (code "109") (name "/RAM1_DATA2") (class "Default")
      (node (ref "HDR1") (pin "53") (pinfunction "53_53") (pintype "passive"))
      (node (ref "U1") (pin "192") (pinfunction "I/O_(161)_192") (pintype "bidirectional"))
    )
    (net (code "110") (name "/RAM1_DATA3") (class "Default")
      (node (ref "HDR1") (pin "57") (pinfunction "57_57") (pintype "passive"))
      (node (ref "U1") (pin "194") (pinfunction "I/O_(182)_194") (pintype "bidirectional"))
    )
    (net (code "111") (name "/RAM1_DATA4") (class "Default")
      (node (ref "HDR1") (pin "55") (pinfunction "55_55") (pintype "passive"))
      (node (ref "U1") (pin "193") (pinfunction "I/O_(170)_193") (pintype "bidirectional"))
    )
    (net (code "112") (name "/RAM1_DATA5") (class "Default")
      (node (ref "HDR1") (pin "51") (pinfunction "51_51") (pintype "passive"))
      (node (ref "U1") (pin "191") (pinfunction "I/O_(158)_191") (pintype "bidirectional"))
    )
    (net (code "113") (name "/RAM1_DATA6") (class "Default")
      (node (ref "HDR1") (pin "47") (pinfunction "47_47") (pintype "passive"))
      (node (ref "U1") (pin "188") (pinfunction "I/O_(152)_188") (pintype "bidirectional"))
    )
    (net (code "114") (name "/RAM1_DATA7") (class "Default")
      (node (ref "HDR1") (pin "43") (pinfunction "43_43") (pintype "passive"))
      (node (ref "U1") (pin "181") (pinfunction "I/O_(120)_181") (pintype "bidirectional"))
    )
    (net (code "115") (name "/RAM1_OE") (class "Default")
      (node (ref "HDR1") (pin "39") (pinfunction "39_39") (pintype "passive"))
      (node (ref "U1") (pin "179") (pinfunction "I/O_(99)_179") (pintype "bidirectional"))
    )
    (net (code "116") (name "/RAM1_WE") (class "Default")
      (node (ref "HDR1") (pin "61") (pinfunction "61_61") (pintype "passive"))
      (node (ref "U1") (pin "199") (pinfunction "I/O_(188)_199") (pintype "bidirectional"))
    )
    (net (code "117") (name "/RAM_ADDR0") (class "Default")
      (node (ref "HDR1") (pin "21") (pinfunction "21_21") (pintype "passive"))
      (node (ref "U1") (pin "166") (pinfunction "I/O_(51)_166") (pintype "bidirectional"))
    )
    (net (code "118") (name "/RAM_ADDR1") (class "Default")
      (node (ref "HDR1") (pin "25") (pinfunction "25_25") (pintype "passive"))
      (node (ref "U1") (pin "168") (pinfunction "I/O_(63)_168") (pintype "bidirectional"))
    )
    (net (code "119") (name "/RAM_ADDR2") (class "Default")
      (node (ref "HDR1") (pin "29") (pinfunction "29_29") (pintype "passive"))
      (node (ref "U1") (pin "173") (pinfunction "I/O_(69)_173") (pintype "bidirectional"))
    )
    (net (code "120") (name "/RAM_ADDR3") (class "Default")
      (node (ref "HDR1") (pin "33") (pinfunction "33_33") (pintype "passive"))
      (node (ref "U1") (pin "175") (pinfunction "I/O_(90)_175") (pintype "bidirectional"))
    )
    (net (code "121") (name "/RAM_ADDR4") (class "Default")
      (node (ref "HDR1") (pin "65") (pinfunction "65_65") (pintype "passive"))
      (node (ref "U1") (pin "201") (pinfunction "I/O_(200)_201") (pintype "bidirectional"))
    )
    (net (code "122") (name "/RAM_ADDR5") (class "Default")
      (node (ref "HDR1") (pin "69") (pinfunction "69_69") (pintype "passive"))
      (node (ref "U1") (pin "203") (pinfunction "I/O,_VREF_(215)_203") (pintype "bidirectional"))
    )
    (net (code "123") (name "/RAM_ADDR6") (class "Default")
      (node (ref "HDR1") (pin "73") (pinfunction "73_73") (pintype "passive"))
      (node (ref "U1") (pin "205") (pinfunction "I/O,_VREF_(233)_205") (pintype "bidirectional"))
    )
    (net (code "124") (name "/RAM_ADDR7") (class "Default")
      (node (ref "HDR1") (pin "77") (pinfunction "77_77") (pintype "passive"))
      (node (ref "U1") (pin "3") (pinfunction "I/O_(257)_3") (pintype "bidirectional"))
    )
    (net (code "125") (name "/RAM_ADDR8") (class "Default")
      (node (ref "HDR1") (pin "75") (pinfunction "75_75") (pintype "passive"))
      (node (ref "U1") (pin "206") (pinfunction "I/O_(248)_206") (pintype "bidirectional"))
    )
    (net (code "126") (name "/RAM_ADDR9") (class "Default")
      (node (ref "HDR1") (pin "71") (pinfunction "71_71") (pintype "passive"))
      (node (ref "U1") (pin "204") (pinfunction "I/O_(218)_204") (pintype "bidirectional"))
    )
    (net (code "127") (name "/RAM_ADDR10") (class "Default")
      (node (ref "HDR1") (pin "67") (pinfunction "67_67") (pintype "passive"))
      (node (ref "U1") (pin "202") (pinfunction "I/O_(212)_202") (pintype "bidirectional"))
    )
    (net (code "128") (name "/RAM_ADDR11") (class "Default")
      (node (ref "HDR1") (pin "63") (pinfunction "63_63") (pintype "passive"))
      (node (ref "U1") (pin "200") (pinfunction "I/O,_VREF_(191)_200") (pintype "bidirectional"))
    )
    (net (code "129") (name "/RAM_ADDR12") (class "Default")
      (node (ref "HDR1") (pin "59") (pinfunction "59_59") (pintype "passive"))
      (node (ref "U1") (pin "195") (pinfunction "I/O_(185)_195") (pintype "bidirectional"))
    )
    (net (code "130") (name "/RAM_ADDR13") (class "Default")
      (node (ref "HDR1") (pin "35") (pinfunction "35_35") (pintype "passive"))
      (node (ref "U1") (pin "176") (pinfunction "I/O_(93)_176") (pintype "bidirectional"))
    )
    (net (code "131") (name "/RAM_ADDR14") (class "Default")
      (node (ref "HDR1") (pin "31") (pinfunction "31_31") (pintype "passive"))
      (node (ref "U1") (pin "174") (pinfunction "I/O_(81)_174") (pintype "bidirectional"))
    )
    (net (code "132") (name "/RAM_ADDR15") (class "Default")
      (node (ref "HDR1") (pin "27") (pinfunction "27_27") (pintype "passive"))
      (node (ref "U1") (pin "172") (pinfunction "I/O_(66)_172") (pintype "bidirectional"))
    )
    (net (code "133") (name "/RAM_ADDR16") (class "Default")
      (node (ref "HDR1") (pin "23") (pinfunction "23_23") (pintype "passive"))
      (node (ref "U1") (pin "167") (pinfunction "I/O,_VREF_(60)_167") (pintype "bidirectional"))
    )
    (net (code "134") (name "/RAM_CS") (class "Default")
      (node (ref "HDR1") (pin "37") (pinfunction "37_37") (pintype "passive"))
      (node (ref "U1") (pin "178") (pinfunction "I/O,_VREF_(96)_178") (pintype "bidirectional"))
    )
    (net (code "135") (name "/RED0") (class "Default")
      (node (ref "HDR1") (pin "6") (pinfunction "6_6") (pintype "passive"))
      (node (ref "U1") (pin "147") (pinfunction "I/O,_VREF_(956)_147") (pintype "bidirectional"))
    )
    (net (code "136") (name "/RED1") (class "Default")
      (node (ref "HDR1") (pin "8") (pinfunction "8_8") (pintype "passive"))
      (node (ref "U1") (pin "146") (pinfunction "I/O_(D1)_(953)_146") (pintype "bidirectional"))
    )
    (net (code "137") (name "/REF_CLK") (class "Default")
      (node (ref "HDR2") (pin "4") (pinfunction "4_4") (pintype "passive"))
      (node (ref "U1") (pin "77") (pinfunction "GCK1_(635)_77") (pintype "input"))
    )
    (net (code "138") (name "/SCL") (class "Default")
      (node (ref "HDR2") (pin "5") (pinfunction "5_5") (pintype "passive"))
      (node (ref "U1") (pin "110") (pinfunction "I/O_(800)_110") (pintype "bidirectional"))
    )
    (net (code "139") (name "/SDA") (class "Default")
      (node (ref "HDR2") (pin "3") (pinfunction "3_3") (pintype "passive"))
      (node (ref "U1") (pin "109") (pinfunction "I/O,_VREF_(785)_109") (pintype "bidirectional"))
    )
    (net (code "140") (name "/SP0") (class "Default")
      (node (ref "HDR2") (pin "79") (pinfunction "79_79") (pintype "passive"))
    )
    (net (code "141") (name "/SP1") (class "Default")
      (node (ref "HDR2") (pin "81") (pinfunction "81_81") (pintype "passive"))
    )
    (net (code "142") (name "/SP2") (class "Default")
      (node (ref "HDR2") (pin "83") (pinfunction "83_83") (pintype "passive"))
    )
    (net (code "143") (name "/SP3") (class "Default")
      (node (ref "HDR2") (pin "85") (pinfunction "85_85") (pintype "passive"))
    )
    (net (code "144") (name "/SP4") (class "Default")
      (node (ref "HDR2") (pin "87") (pinfunction "87_87") (pintype "passive"))
    )
    (net (code "145") (name "/SP5") (class "Default")
      (node (ref "HDR2") (pin "89") (pinfunction "89_89") (pintype "passive"))
    )
    (net (code "146") (name "/SP6") (class "Default")
      (node (ref "HDR2") (pin "91") (pinfunction "91_91") (pintype "passive"))
    )
    (net (code "147") (name "/SP7") (class "Default")
      (node (ref "HDR2") (pin "90") (pinfunction "90_90") (pintype "passive"))
    )
    (net (code "148") (name "/SP8") (class "Default")
      (node (ref "HDR2") (pin "92") (pinfunction "92_92") (pintype "passive"))
    )
    (net (code "149") (name "/SP9") (class "Default")
      (node (ref "HDR2") (pin "88") (pinfunction "88_88") (pintype "passive"))
    )
    (net (code "150") (name "/SP10") (class "Default")
      (node (ref "HDR2") (pin "86") (pinfunction "86_86") (pintype "passive"))
    )
    (net (code "151") (name "/SP11") (class "Default")
      (node (ref "HDR2") (pin "84") (pinfunction "84_84") (pintype "passive"))
    )
    (net (code "152") (name "/SP12") (class "Default")
      (node (ref "HDR2") (pin "82") (pinfunction "82_82") (pintype "passive"))
    )
    (net (code "153") (name "/SP13") (class "Default")
      (node (ref "HDR2") (pin "80") (pinfunction "80_80") (pintype "passive"))
    )
    (net (code "154") (name "/SP14") (class "Default")
      (node (ref "HDR2") (pin "78") (pinfunction "78_78") (pintype "passive"))
    )
    (net (code "155") (name "/SP15") (class "Default")
      (node (ref "HDR2") (pin "76") (pinfunction "76_76") (pintype "passive"))
    )
    (net (code "156") (name "/SPI_CLK") (class "Default")
      (node (ref "HDR1") (pin "46") (pinfunction "46_46") (pintype "passive"))
      (node (ref "U1") (pin "17") (pinfunction "I/O_(344)_17") (pintype "bidirectional"))
    )
    (net (code "157") (name "/SPI_DIN") (class "Default")
      (node (ref "HDR1") (pin "44") (pinfunction "44_44") (pintype "passive"))
      (node (ref "U1") (pin "18") (pinfunction "I/O_(347)_18") (pintype "bidirectional"))
    )
    (net (code "158") (name "/SPI_DOUT") (class "Default")
      (node (ref "HDR1") (pin "50") (pinfunction "50_50") (pintype "passive"))
      (node (ref "U1") (pin "15") (pinfunction "I/O_(323)_15") (pintype "bidirectional"))
    )
    (net (code "159") (name "/SPI_MODE") (class "Default")
      (node (ref "HDR1") (pin "52") (pinfunction "52_52") (pintype "passive"))
      (node (ref "U1") (pin "14") (pinfunction "I/O_(320)_14") (pintype "bidirectional"))
    )
    (net (code "160") (name "/SPI_SEL") (class "Default")
      (node (ref "HDR1") (pin "48") (pinfunction "48_48") (pintype "passive"))
      (node (ref "U1") (pin "16") (pinfunction "I/O_(335)_16") (pintype "bidirectional"))
    )
    (net (code "161") (name "/SW0") (class "Default")
      (node (ref "HDR2") (pin "44") (pinfunction "44_44") (pintype "passive"))
      (node (ref "U1") (pin "75") (pinfunction "I/O_(620)_75") (pintype "bidirectional"))
    )
    (net (code "162") (name "/SW1") (class "Default")
      (node (ref "HDR2") (pin "46") (pinfunction "46_46") (pintype "passive"))
      (node (ref "U1") (pin "74") (pinfunction "I/O_(608)_74") (pintype "bidirectional"))
    )
    (net (code "163") (name "/SW2") (class "Default")
      (node (ref "HDR2") (pin "48") (pinfunction "48_48") (pintype "passive"))
      (node (ref "U1") (pin "73") (pinfunction "I/O,_VREF_(605)_73") (pintype "bidirectional"))
    )
    (net (code "164") (name "/SW3") (class "Default")
      (node (ref "HDR2") (pin "50") (pinfunction "50_50") (pintype "passive"))
      (node (ref "U1") (pin "71") (pinfunction "I/O_(602)_71") (pintype "bidirectional"))
    )
    (net (code "165") (name "/SW4") (class "Default")
      (node (ref "HDR2") (pin "52") (pinfunction "52_52") (pintype "passive"))
      (node (ref "U1") (pin "70") (pinfunction "I/O_(599)_70") (pintype "bidirectional"))
    )
    (net (code "166") (name "/SW5") (class "Default")
      (node (ref "HDR2") (pin "54") (pinfunction "54_54") (pintype "passive"))
      (node (ref "U1") (pin "69") (pinfunction "I/O_(590)_69") (pintype "bidirectional"))
    )
    (net (code "167") (name "/SW6") (class "Default")
      (node (ref "HDR2") (pin "56") (pinfunction "56_56") (pintype "passive"))
      (node (ref "U1") (pin "68") (pinfunction "I/O_(578)_68") (pintype "bidirectional"))
    )
    (net (code "168") (name "/SW7") (class "Default")
      (node (ref "HDR2") (pin "58") (pinfunction "58_58") (pintype "passive"))
      (node (ref "U1") (pin "67") (pinfunction "I/O_(575)_67") (pintype "bidirectional"))
    )
    (net (code "169") (name "/SWC0") (class "Default")
      (node (ref "HDR2") (pin "18") (pinfunction "18_18") (pintype "passive"))
      (node (ref "U1") (pin "96") (pinfunction "I/O_(709)_96") (pintype "bidirectional"))
    )
    (net (code "170") (name "/SWC1") (class "Default")
      (node (ref "HDR2") (pin "16") (pinfunction "16_16") (pintype "passive"))
      (node (ref "U1") (pin "98") (pinfunction "I/O,_VREF_(724)_98") (pintype "bidirectional"))
    )
    (net (code "171") (name "/SWC2") (class "Default")
      (node (ref "HDR2") (pin "14") (pinfunction "14_14") (pintype "passive"))
      (node (ref "U1") (pin "99") (pinfunction "I/O_(727)_99") (pintype "bidirectional"))
    )
    (net (code "172") (name "/SWC3") (class "Default")
      (node (ref "HDR2") (pin "6") (pinfunction "6_6") (pintype "passive"))
      (node (ref "U1") (pin "108") (pinfunction "I/O_(D7)_(770)_108") (pintype "bidirectional"))
    )
    (net (code "173") (name "/SWR0") (class "Default")
      (node (ref "HDR2") (pin "20") (pinfunction "20_20") (pintype "passive"))
      (node (ref "U1") (pin "95") (pinfunction "I/O,_VREF_(700)_95") (pintype "bidirectional"))
    )
    (net (code "174") (name "/SWR1") (class "Default")
      (node (ref "HDR2") (pin "12") (pinfunction "12_12") (pintype "passive"))
      (node (ref "U1") (pin "100") (pinfunction "I/O,_VREF_(742)_100") (pintype "bidirectional"))
    )
    (net (code "175") (name "/SWR2") (class "Default")
      (node (ref "HDR2") (pin "10") (pinfunction "10_10") (pintype "passive"))
      (node (ref "U1") (pin "101") (pinfunction "I/O_(757)_101") (pintype "bidirectional"))
    )
    (net (code "176") (name "/SWR3") (class "Default")
      (node (ref "HDR2") (pin "8") (pinfunction "8_8") (pintype "passive"))
      (node (ref "U1") (pin "102") (pinfunction "I/O_(760)_102") (pintype "bidirectional"))
    )
    (net (code "177") (name "/TEST") (class "Default")
      (node (ref "HDR1") (pin "81") (pinfunction "81_81") (pintype "passive"))
      (node (ref "U1") (pin "5") (pinfunction "I/O_(287)_5") (pintype "bidirectional"))
    )
    (net (code "178") (name "/VDRIVE") (class "Default")
      (node (ref "HDR1") (pin "20") (pinfunction "20_20") (pintype "passive"))
      (node (ref "U1") (pin "136") (pinfunction "I/O,_VREF_(920)_136") (pintype "bidirectional"))
    )
    (net (code "179") (name "/VREF") (class "Default")
      (node (ref "HDR1") (pin "91") (pinfunction "91_91") (pintype "passive"))
      (node (ref "R1") (pin "2") (pinfunction "2_2") (pintype "passive"))
      (node (ref "R2") (pin "1") (pinfunction "1_1") (pintype "passive"))
    )
    (net (code "180") (name "5V") (class "Default")
      (node (ref "HDR1") (pin "97") (pinfunction "97_97") (pintype "passive"))
      (node (ref "HDR1") (pin "99") (pinfunction "99_99") (pintype "passive"))
      (node (ref "HDR2") (pin "97") (pinfunction "97_97") (pintype "passive"))
      (node (ref "HDR2") (pin "99") (pinfunction "99_99") (pintype "passive"))
    )
    (net (code "181") (name "GND") (class "Default")
      (node (ref "C1") (pin "1") (pinfunction "1_1") (pintype "passive"))
      (node (ref "C10") (pin "2") (pinfunction "2_2") (pintype "passive"))
      (node (ref "C11") (pin "2") (pinfunction "2_2") (pintype "passive"))
      (node (ref "C12") (pin "2") (pinfunction "2_2") (pintype "passive"))
      (node (ref "C13") (pin "2") (pinfunction "2_2") (pintype "passive"))
      (node (ref "C14") (pin "2") (pinfunction "2_2") (pintype "passive"))
      (node (ref "C15") (pin "2") (pinfunction "2_2") (pintype "passive"))
      (node (ref "C16") (pin "2") (pinfunction "2_2") (pintype "passive"))
      (node (ref "C17") (pin "1") (pinfunction "1_1") (pintype "passive"))
      (node (ref "C18") (pin "1") (pinfunction "1_1") (pintype "passive"))
      (node (ref "C19") (pin "1") (pinfunction "1_1") (pintype "passive"))
      (node (ref "C2") (pin "2") (pinfunction "2_2") (pintype "passive"))
      (node (ref "C20") (pin "1") (pinfunction "1_1") (pintype "passive"))
      (node (ref "C21") (pin "1") (pinfunction "1_1") (pintype "passive"))
      (node (ref "C22") (pin "2") (pinfunction "2_2") (pintype "passive"))
      (node (ref "C23") (pin "2") (pinfunction "2_2") (pintype "passive"))
      (node (ref "C24") (pin "2") (pinfunction "2_2") (pintype "passive"))
      (node (ref "C25") (pin "1") (pinfunction "1_1") (pintype "passive"))
      (node (ref "C26") (pin "1") (pinfunction "1_1") (pintype "passive"))
      (node (ref "C27") (pin "1") (pinfunction "1_1") (pintype "passive"))
      (node (ref "C28") (pin "1") (pinfunction "1_1") (pintype "passive"))
      (node (ref "C29") (pin "1") (pinfunction "1_1") (pintype "passive"))
      (node (ref "C3") (pin "2") (pinfunction "2_2") (pintype "passive"))
      (node (ref "C30") (pin "2") (pinfunction "2_2") (pintype "passive"))
      (node (ref "C31") (pin "2") (pinfunction "2_2") (pintype "passive"))
      (node (ref "C32") (pin "2") (pinfunction "2_2") (pintype "passive"))
      (node (ref "C33") (pin "2") (pinfunction "2_2") (pintype "passive"))
      (node (ref "C4") (pin "2") (pinfunction "2_2") (pintype "passive"))
      (node (ref "C5") (pin "2") (pinfunction "2_2") (pintype "passive"))
      (node (ref "C6") (pin "2") (pinfunction "2_2") (pintype "passive"))
      (node (ref "C7") (pin "2") (pinfunction "2_2") (pintype "passive"))
      (node (ref "C8") (pin "2") (pinfunction "2_2") (pintype "passive"))
      (node (ref "C9") (pin "2") (pinfunction "2_2") (pintype "passive"))
      (node (ref "HDR1") (pin "1") (pinfunction "1_1") (pintype "passive"))
      (node (ref "HDR1") (pin "100") (pinfunction "100_100") (pintype "passive"))
      (node (ref "HDR1") (pin "36") (pinfunction "36_36") (pintype "passive"))
      (node (ref "HDR1") (pin "38") (pinfunction "38_38") (pintype "passive"))
      (node (ref "HDR1") (pin "40") (pinfunction "40_40") (pintype "passive"))
      (node (ref "HDR1") (pin "42") (pinfunction "42_42") (pintype "passive"))
      (node (ref "HDR1") (pin "98") (pinfunction "98_98") (pintype "passive"))
      (node (ref "HDR2") (pin "1") (pinfunction "1_1") (pintype "passive"))
      (node (ref "HDR2") (pin "100") (pinfunction "100_100") (pintype "passive"))
      (node (ref "HDR2") (pin "98") (pinfunction "98_98") (pintype "passive"))
      (node (ref "LED2") (pin "2") (pinfunction "K_2") (pintype "passive"))
      (node (ref "R2") (pin "2") (pinfunction "2_2") (pintype "passive"))
      (node (ref "U1") (pin "1") (pinfunction "GND_1") (pintype "power_in"))
      (node (ref "U1") (pin "103") (pinfunction "GND_103") (pintype "power_in"))
      (node (ref "U1") (pin "11") (pinfunction "GND_11") (pintype "power_in"))
      (node (ref "U1") (pin "116") (pinfunction "GND_116") (pintype "power_in"))
      (node (ref "U1") (pin "124") (pinfunction "GND_124") (pintype "power_in"))
      (node (ref "U1") (pin "131") (pinfunction "GND_131") (pintype "power_in"))
      (node (ref "U1") (pin "137") (pinfunction "GND_137") (pintype "power_in"))
      (node (ref "U1") (pin "145") (pinfunction "GND_145") (pintype "power_in"))
      (node (ref "U1") (pin "158") (pinfunction "GND_158") (pintype "power_in"))
      (node (ref "U1") (pin "169") (pinfunction "GND_169") (pintype "power_in"))
      (node (ref "U1") (pin "177") (pinfunction "GND_177") (pintype "power_in"))
      (node (ref "U1") (pin "183") (pinfunction "GND_183") (pintype "power_in"))
      (node (ref "U1") (pin "19") (pinfunction "GND_19") (pintype "power_in"))
      (node (ref "U1") (pin "190") (pinfunction "GND_190") (pintype "power_in"))
      (node (ref "U1") (pin "198") (pinfunction "GND_198") (pintype "power_in"))
      (node (ref "U1") (pin "25") (pinfunction "GND_25") (pintype "power_in"))
      (node (ref "U1") (pin "32") (pinfunction "GND_32") (pintype "power_in"))
      (node (ref "U1") (pin "40") (pinfunction "GND_40") (pintype "power_in"))
      (node (ref "U1") (pin "51") (pinfunction "GND_51") (pintype "power_in"))
      (node (ref "U1") (pin "64") (pinfunction "GND_64") (pintype "power_in"))
      (node (ref "U1") (pin "72") (pinfunction "GND_72") (pintype "power_in"))
      (node (ref "U1") (pin "79") (pinfunction "GND_79") (pintype "power_in"))
      (node (ref "U1") (pin "85") (pinfunction "GND_85") (pintype "power_in"))
      (node (ref "U1") (pin "93") (pinfunction "GND_93") (pintype "power_in"))
      (node (ref "U2") (pin "3") (pinfunction "GND_3") (pintype "power_in"))
    )
    (net (code "182") (name "Net-(LED1-A)") (class "Default")
      (node (ref "LED1") (pin "1") (pinfunction "A_1") (pintype "passive"))
      (node (ref "R4") (pin "1") (pinfunction "1_1") (pintype "passive"))
    )
    (net (code "183") (name "Net-(LED1-K)") (class "Default")
      (node (ref "LED1") (pin "2") (pinfunction "K_2") (pintype "passive"))
      (node (ref "U2") (pin "4") (pinfunction "Y_4") (pintype "output"))
    )
    (net (code "184") (name "Net-(LED2-A)") (class "Default")
      (node (ref "LED2") (pin "1") (pinfunction "A_1") (pintype "passive"))
      (node (ref "R3") (pin "2") (pinfunction "2_2") (pintype "passive"))
    )
    (net (code "185") (name "VCC") (class "Default")
      (node (ref "C1") (pin "2") (pinfunction "2_2") (pintype "passive"))
      (node (ref "C14") (pin "1") (pinfunction "1_1") (pintype "passive"))
      (node (ref "C15") (pin "1") (pinfunction "1_1") (pintype "passive"))
      (node (ref "C16") (pin "1") (pinfunction "1_1") (pintype "passive"))
      (node (ref "C17") (pin "2") (pinfunction "2_2") (pintype "passive"))
      (node (ref "C18") (pin "2") (pinfunction "2_2") (pintype "passive"))
      (node (ref "C19") (pin "2") (pinfunction "2_2") (pintype "passive"))
      (node (ref "C20") (pin "2") (pinfunction "2_2") (pintype "passive"))
      (node (ref "C21") (pin "2") (pinfunction "2_2") (pintype "passive"))
      (node (ref "C22") (pin "1") (pinfunction "1_1") (pintype "passive"))
      (node (ref "C23") (pin "1") (pinfunction "1_1") (pintype "passive"))
      (node (ref "C24") (pin "1") (pinfunction "1_1") (pintype "passive"))
      (node (ref "C25") (pin "2") (pinfunction "2_2") (pintype "passive"))
      (node (ref "C26") (pin "2") (pinfunction "2_2") (pintype "passive"))
      (node (ref "C27") (pin "2") (pinfunction "2_2") (pintype "passive"))
      (node (ref "C28") (pin "2") (pinfunction "2_2") (pintype "passive"))
      (node (ref "C29") (pin "2") (pinfunction "2_2") (pintype "passive"))
      (node (ref "C32") (pin "1") (pinfunction "1_1") (pintype "passive"))
      (node (ref "C33") (pin "1") (pinfunction "1_1") (pintype "passive"))
      (node (ref "HDR1") (pin "34") (pinfunction "34_34") (pintype "passive"))
      (node (ref "HDR1") (pin "94") (pinfunction "94_94") (pintype "passive"))
      (node (ref "HDR1") (pin "96") (pinfunction "96_96") (pintype "passive"))
      (node (ref "HDR2") (pin "94") (pinfunction "94_94") (pintype "passive"))
      (node (ref "HDR2") (pin "96") (pinfunction "96_96") (pintype "passive"))
      (node (ref "R3") (pin "1") (pinfunction "1_1") (pintype "passive"))
      (node (ref "R4") (pin "2") (pinfunction "2_2") (pintype "passive"))
      (node (ref "R5") (pin "1") (pinfunction "1_1") (pintype "passive"))
      (node (ref "R8") (pin "1") (pinfunction "1_1") (pintype "passive"))
      (node (ref "R9") (pin "1") (pinfunction "1_1") (pintype "passive"))
      (node (ref "U1") (pin "105") (pinfunction "VCCO_105") (pintype "power_in"))
      (node (ref "U1") (pin "117") (pinfunction "VCCO_117") (pintype "power_in"))
      (node (ref "U1") (pin "12") (pinfunction "VCCO_12") (pintype "power_in"))
      (node (ref "U1") (pin "130") (pinfunction "VCCO_130") (pintype "power_in"))
      (node (ref "U1") (pin "144") (pinfunction "VCCO_144") (pintype "power_in"))
      (node (ref "U1") (pin "156") (pinfunction "VCCO_156") (pintype "power_in"))
      (node (ref "U1") (pin "170") (pinfunction "VCCO_170") (pintype "power_in"))
      (node (ref "U1") (pin "184") (pinfunction "VCCO_184") (pintype "power_in"))
      (node (ref "U1") (pin "197") (pinfunction "VCCO_197") (pintype "power_in"))
      (node (ref "U1") (pin "208") (pinfunction "VCCO_208") (pintype "power_in"))
      (node (ref "U1") (pin "26") (pinfunction "VCCO_26") (pintype "power_in"))
      (node (ref "U1") (pin "39") (pinfunction "VCCO_39") (pintype "power_in"))
      (node (ref "U1") (pin "53") (pinfunction "VCCO_53") (pintype "power_in"))
      (node (ref "U1") (pin "65") (pinfunction "VCCO_65") (pintype "power_in"))
      (node (ref "U1") (pin "78") (pinfunction "VCCO_78") (pintype "power_in"))
      (node (ref "U1") (pin "92") (pinfunction "VCCO_92") (pintype "power_in"))
      (node (ref "U2") (pin "5") (pinfunction "VCC_5") (pintype "power_in"))
    )
    (net (code "186") (name "VCCINT") (class "Default")
      (node (ref "C10") (pin "1") (pinfunction "1_1") (pintype "passive"))
      (node (ref "C11") (pin "1") (pinfunction "1_1") (pintype "passive"))
      (node (ref "C12") (pin "1") (pinfunction "1_1") (pintype "passive"))
      (node (ref "C13") (pin "1") (pinfunction "1_1") (pintype "passive"))
      (node (ref "C2") (pin "1") (pinfunction "1_1") (pintype "passive"))
      (node (ref "C3") (pin "1") (pinfunction "1_1") (pintype "passive"))
      (node (ref "C30") (pin "1") (pinfunction "1_1") (pintype "passive"))
      (node (ref "C31") (pin "1") (pinfunction "1_1") (pintype "passive"))
      (node (ref "C4") (pin "1") (pinfunction "1_1") (pintype "passive"))
      (node (ref "C5") (pin "1") (pinfunction "1_1") (pintype "passive"))
      (node (ref "C6") (pin "1") (pinfunction "1_1") (pintype "passive"))
      (node (ref "C7") (pin "1") (pinfunction "1_1") (pintype "passive"))
      (node (ref "C8") (pin "1") (pinfunction "1_1") (pintype "passive"))
      (node (ref "C9") (pin "1") (pinfunction "1_1") (pintype "passive"))
      (node (ref "HDR1") (pin "93") (pinfunction "93_93") (pintype "passive"))
      (node (ref "HDR1") (pin "95") (pinfunction "95_95") (pintype "passive"))
      (node (ref "HDR2") (pin "93") (pinfunction "93_93") (pintype "passive"))
      (node (ref "HDR2") (pin "95") (pinfunction "95_95") (pintype "passive"))
      (node (ref "R1") (pin "1") (pinfunction "1_1") (pintype "passive"))
      (node (ref "U1") (pin "118") (pinfunction "VCCINT_118") (pintype "power_in"))
      (node (ref "U1") (pin "128") (pinfunction "VCCINT_128") (pintype "power_in"))
      (node (ref "U1") (pin "13") (pinfunction "VCCINT_13") (pintype "power_in"))
      (node (ref "U1") (pin "143") (pinfunction "VCCINT_143") (pintype "power_in"))
      (node (ref "U1") (pin "171") (pinfunction "VCCINT_171") (pintype "power_in"))
      (node (ref "U1") (pin "186") (pinfunction "VCCINT_186") (pintype "power_in"))
      (node (ref "U1") (pin "196") (pinfunction "VCCINT_196") (pintype "power_in"))
      (node (ref "U1") (pin "28") (pinfunction "VCCINT_28") (pintype "power_in"))
      (node (ref "U1") (pin "38") (pinfunction "VCCINT_38") (pintype "power_in"))
      (node (ref "U1") (pin "66") (pinfunction "VCCINT_66") (pintype "power_in"))
      (node (ref "U1") (pin "76") (pinfunction "VCCINT_76") (pintype "power_in"))
      (node (ref "U1") (pin "91") (pinfunction "VCCINT_91") (pintype "power_in"))
    )
    (net (code "187") (name "unconnected-(U1A-I{slash}O_(548)-Pad60)") (class "Default")
      (node (ref "U1") (pin "60") (pinfunction "I/O_(548)_60") (pintype "bidirectional+no_connect"))
    )
    (net (code "188") (name "unconnected-(U1A-I{slash}O_(977)-Pad149)") (class "Default")
      (node (ref "U1") (pin "149") (pinfunction "I/O_(977)_149") (pintype "bidirectional+no_connect"))
    )
    (net (code "189") (name "unconnected-(U1B-NC-Pad55)") (class "Default")
      (node (ref "U1") (pin "55") (pinfunction "NC_55") (pintype "passive+no_connect"))
    )
    (net (code "190") (name "unconnected-(U1B-NC-Pad56)") (class "Default")
      (node (ref "U1") (pin "56") (pinfunction "NC_56") (pintype "passive+no_connect"))
    )
    (net (code "191") (name "unconnected-(U2-NC-Pad1)") (class "Default")
      (node (ref "U2") (pin "1") (pinfunction "NC_1") (pintype "passive"))
    )
  )
)
